# TPS61280x_Module.net
KiCad netlist of a schematic drawn in EAGLE
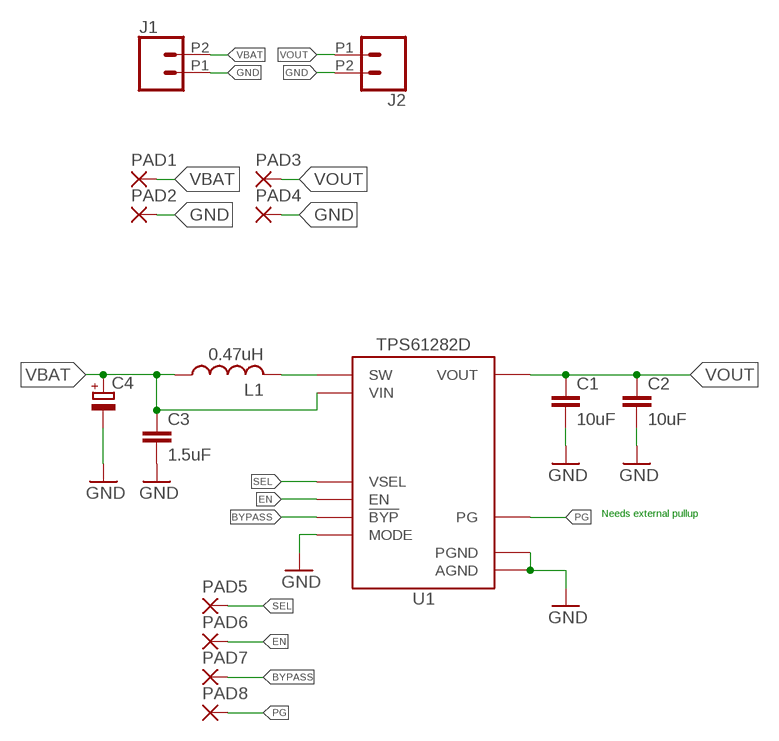
[diagram p0: schematic, sheet 1]

(export (version "E")
  (design (tool "Eeschema 10.0.6"))
  (components
    (comp (ref "C1")
      (value "10uF")
      (footprint "eagle-import:C0805")
      (fields (field (name "MF") "Murata") (field (name "MPN") "GRM21BR61C106KE15K"))
      (libsource (lib "eagle-import") (part "C-EUC080510UF"))
    )
    (comp (ref "C2")
      (value "10uF")
      (footprint "eagle-import:C0805")
      (fields (field (name "MF") "Murata") (field (name "MPN") "GRM21BR61C106KE15K"))
      (libsource (lib "eagle-import") (part "C-EUC080510UF"))
    )
    (comp (ref "C3")
      (value "1.5uF")
      (footprint "eagle-import:C0805")
      (fields (field (name "MF") "Kemet") (field (name "MPN") "C0805C155K4RACTU"))
      (libsource (lib "eagle-import") (part "C-EUC08051.5UF"))
    )
    (comp (ref "C4")
      (value "CTANT_EU2917")
      (footprint "eagle-import:C2917")
      (libsource (lib "eagle-import") (part "CTANT_EU2917"))
    )
    (comp (ref "J1")
      (value "CONN_022.54_SCREW_ROUND")
      (footprint "eagle-import:1X02_2.54_SCREWTERM_ROUND")
      (fields (field (name "MF") "OnShore") (field (name "MPN") "OSTVN02A150"))
      (libsource (lib "eagle-import") (part "CONN_022.54_SCREW_ROUND"))
    )
    (comp (ref "J2")
      (value "CONN_022.54_SCREW_ROUND")
      (footprint "eagle-import:1X02_2.54_SCREWTERM_ROUND")
      (fields (field (name "MF") "OnShore") (field (name "MPN") "OSTVN02A150"))
      (libsource (lib "eagle-import") (part "CONN_022.54_SCREW_ROUND"))
    )
    (comp (ref "L1")
      (value "0.47uH")
      (footprint "eagle-import:WE-MAPI(4.1X4.1)")
      (libsource (lib "eagle-import") (part "INDUCTOR_MAPI_4.1X4.1"))
    )
    (comp (ref "PAD1")
      (value "SMD5")
      (footprint "eagle-import:SMD2,54-5,08")
      (libsource (lib "eagle-import") (part "SMD5"))
    )
    (comp (ref "PAD2")
      (value "SMD5")
      (footprint "eagle-import:SMD2,54-5,08")
      (libsource (lib "eagle-import") (part "SMD5"))
    )
    (comp (ref "PAD3")
      (value "SMD5")
      (footprint "eagle-import:SMD2,54-5,08")
      (libsource (lib "eagle-import") (part "SMD5"))
    )
    (comp (ref "PAD4")
      (value "SMD5")
      (footprint "eagle-import:SMD2,54-5,08")
      (libsource (lib "eagle-import") (part "SMD5"))
    )
    (comp (ref "PAD5")
      (value "SMD2")
      (footprint "eagle-import:SMD1,27-2,54")
      (fields (field (name "MPN") "DNP"))
      (libsource (lib "eagle-import") (part "SMD2"))
    )
    (comp (ref "PAD6")
      (value "SMD2")
      (footprint "eagle-import:SMD1,27-2,54")
      (fields (field (name "MPN") "DNP"))
      (libsource (lib "eagle-import") (part "SMD2"))
    )
    (comp (ref "PAD7")
      (value "SMD2")
      (footprint "eagle-import:SMD1,27-2,54")
      (fields (field (name "MPN") "DNP"))
      (libsource (lib "eagle-import") (part "SMD2"))
    )
    (comp (ref "PAD8")
      (value "SMD2")
      (footprint "eagle-import:SMD1,27-2,54")
      (fields (field (name "MPN") "DNP"))
      (libsource (lib "eagle-import") (part "SMD2"))
    )
    (comp (ref "U1")
      (value "TPS61282D")
      (footprint "eagle-import:YFP0016")
      (fields (field (name "DISP") "TPS61282D") (field (name "MF") "TI") (field (name "MPN") "TPS61282DYFFT"))
      (libsource (lib "eagle-import") (part "TPS61282D"))
    )
  )
  (nets
    (net (code "1") (name "BYPASS") (class "Default")
      (node (ref "PAD7") (pin "1") (pinfunction "P_1") (pintype "passive"))
      (node (ref "U1") (pin "C1") (pinfunction "~{BYP}_C1") (pintype "input"))
    )
    (net (code "2") (name "EN") (class "Default")
      (node (ref "PAD6") (pin "1") (pinfunction "P_1") (pintype "passive"))
      (node (ref "U1") (pin "A1") (pinfunction "EN_A1") (pintype "input"))
    )
    (net (code "3") (name "GND") (class "Default")
      (node (ref "C1") (pin "2") (pinfunction "2_2") (pintype "passive"))
      (node (ref "C2") (pin "2") (pinfunction "2_2") (pintype "passive"))
      (node (ref "C3") (pin "2") (pinfunction "2_2") (pintype "passive"))
      (node (ref "C4") (pin "-") (pinfunction "-_-") (pintype "passive"))
      (node (ref "J1") (pin "P1") (pinfunction "1_P1") (pintype "passive"))
      (node (ref "J2") (pin "P2") (pinfunction "2_P2") (pintype "passive"))
      (node (ref "PAD2") (pin "1") (pinfunction "P_1") (pintype "passive"))
      (node (ref "PAD4") (pin "1") (pinfunction "P_1") (pintype "passive"))
      (node (ref "U1") (pin "B2") (pinfunction "MODE_B2") (pintype "input"))
      (node (ref "U1") (pin "C2") (pinfunction "AGND_C2") (pintype "power_in"))
      (node (ref "U1") (pin "D1") (pinfunction "AGND_D1") (pintype "power_in"))
      (node (ref "U1") (pin "D2") (pinfunction "PGND_D2") (pintype "power_in"))
      (node (ref "U1") (pin "D3") (pinfunction "PGND_D3") (pintype "power_in"))
      (node (ref "U1") (pin "D4") (pinfunction "PGND_D4") (pintype "power_in"))
    )
    (net (code "4") (name "Net-(L1-2)") (class "Default")
      (node (ref "L1") (pin "P$2") (pinfunction "2_P$2") (pintype "passive"))
      (node (ref "U1") (pin "C3") (pinfunction "SW_C3") (pintype "power_in"))
      (node (ref "U1") (pin "C4") (pinfunction "SW_C4") (pintype "power_in"))
    )
    (net (code "5") (name "PG") (class "Default")
      (node (ref "PAD8") (pin "1") (pinfunction "P_1") (pintype "passive"))
      (node (ref "U1") (pin "A2") (pinfunction "PG_A2") (pintype "open_collector"))
    )
    (net (code "6") (name "SEL") (class "Default")
      (node (ref "PAD5") (pin "1") (pinfunction "P_1") (pintype "passive"))
      (node (ref "U1") (pin "B1") (pinfunction "VSEL_B1") (pintype "input"))
    )
    (net (code "7") (name "VBAT") (class "Default")
      (node (ref "C3") (pin "1") (pinfunction "1_1") (pintype "passive"))
      (node (ref "C4") (pin "+") (pinfunction "+_+") (pintype "passive"))
      (node (ref "J1") (pin "P2") (pinfunction "2_P2") (pintype "passive"))
      (node (ref "L1") (pin "P$1") (pinfunction "1_P$1") (pintype "passive"))
      (node (ref "PAD1") (pin "1") (pinfunction "P_1") (pintype "passive"))
      (node (ref "U1") (pin "A3") (pinfunction "VIN_A3") (pintype "power_in"))
      (node (ref "U1") (pin "A4") (pinfunction "VIN_A4") (pintype "power_in"))
    )
    (net (code "8") (name "VOUT") (class "Default")
      (node (ref "C1") (pin "1") (pinfunction "1_1") (pintype "passive"))
      (node (ref "C2") (pin "1") (pinfunction "1_1") (pintype "passive"))
      (node (ref "J2") (pin "P1") (pinfunction "1_P1") (pintype "passive"))
      (node (ref "PAD3") (pin "1") (pinfunction "P_1") (pintype "passive"))
      (node (ref "U1") (pin "B3") (pinfunction "VOUT_B3") (pintype "power_in"))
      (node (ref "U1") (pin "B4") (pinfunction "VOUT_B4") (pintype "power_in"))
    )
  )
)
